# usbSimStepper_v1_0a.net
KiCad netlist of a schematic drawn in EAGLE
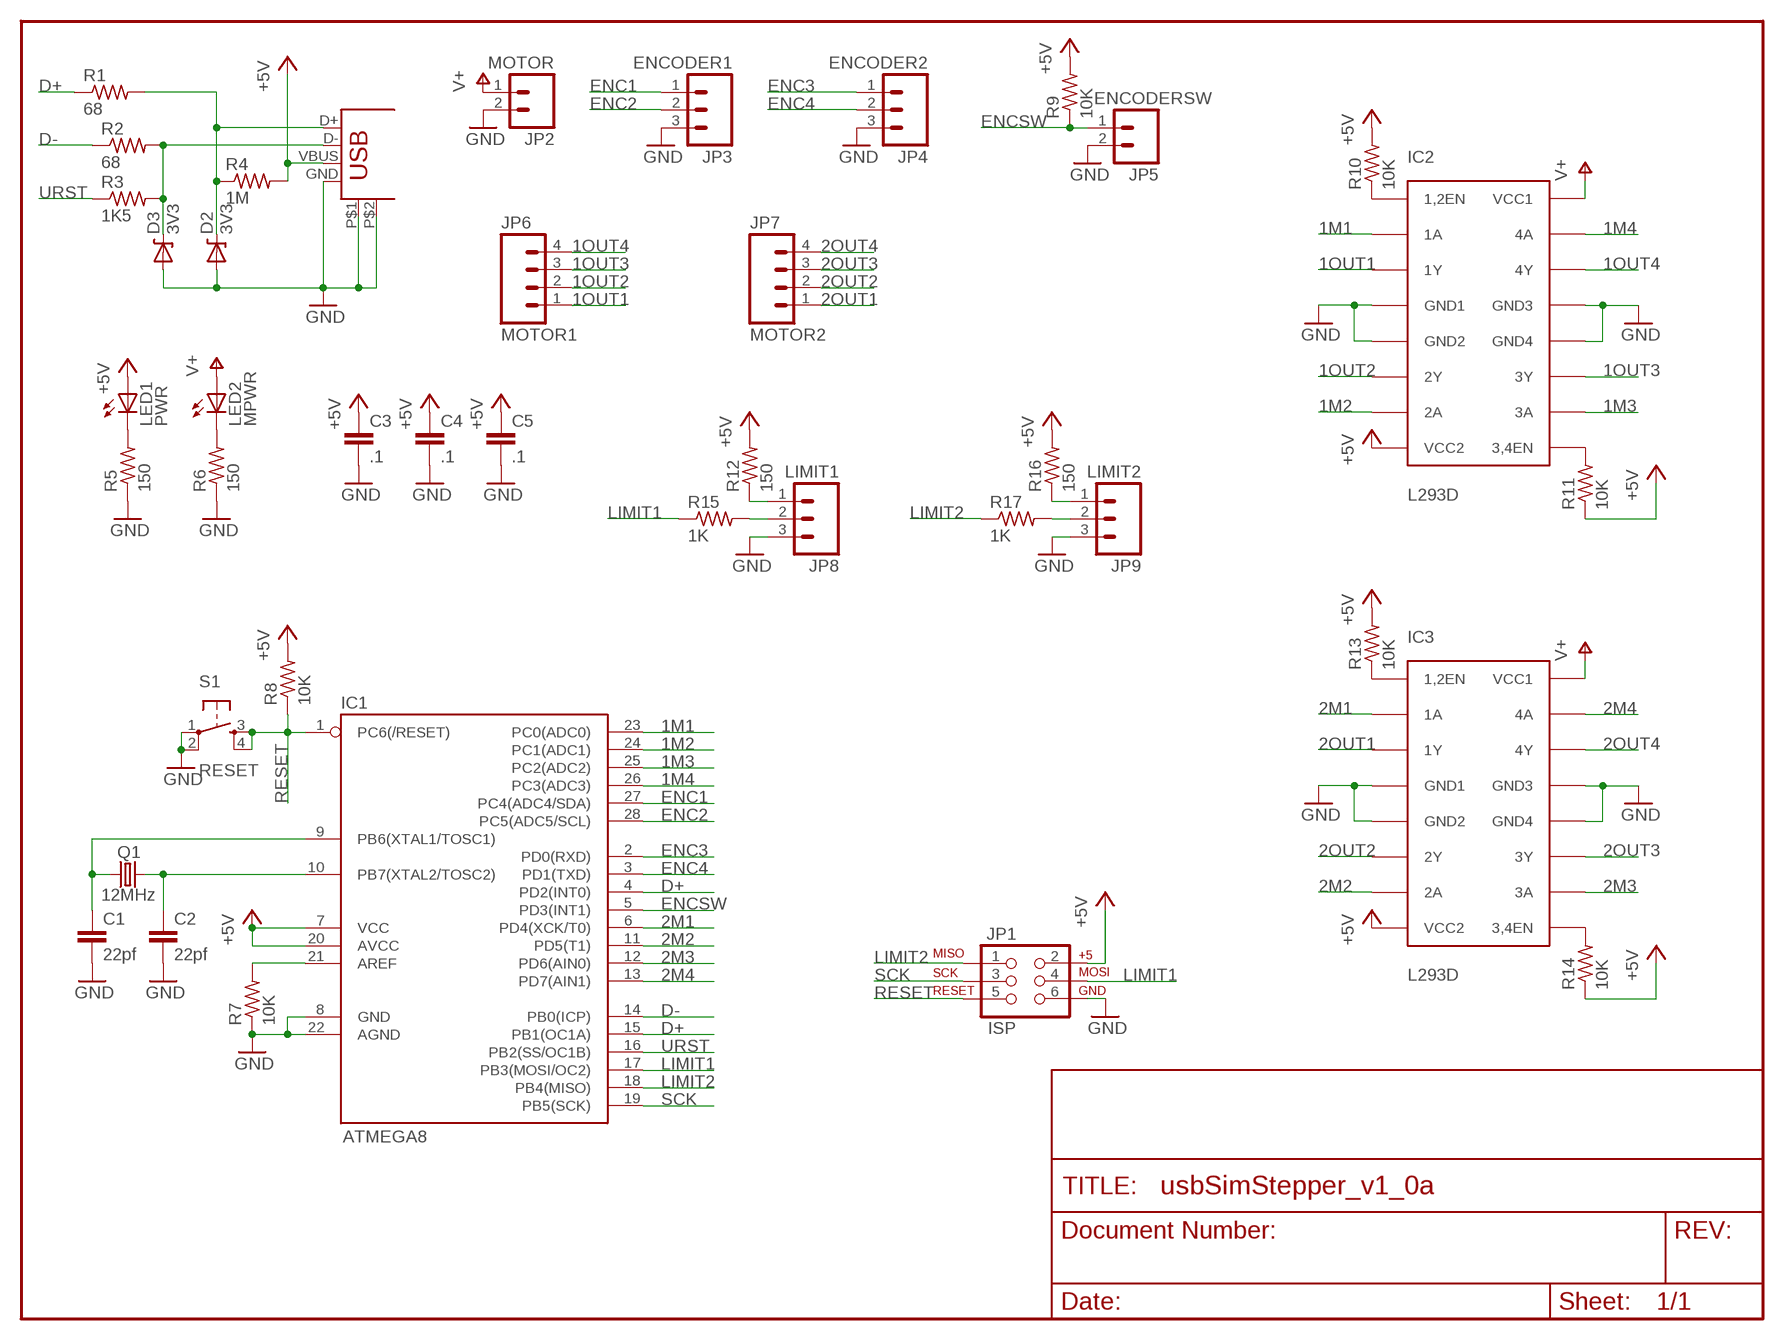
[diagram p0: schematic, sheet 1]

(export (version "E")
  (design (tool "Eeschema 10.0.6"))
  (components
    (comp (ref "C1")
      (value "22pf")
      (footprint "eagle-import:CAP-PTH-SMALL2")
      (libsource (lib "eagle-import") (part "CAPPTH2"))
    )
    (comp (ref "C2")
      (value "22pf")
      (footprint "eagle-import:CAP-PTH-SMALL2")
      (libsource (lib "eagle-import") (part "CAPPTH2"))
    )
    (comp (ref "C3")
      (value ".1")
      (footprint "eagle-import:CAP-PTH-SMALL2")
      (libsource (lib "eagle-import") (part "CAPPTH2"))
    )
    (comp (ref "C4")
      (value ".1")
      (footprint "eagle-import:CAP-PTH-SMALL2")
      (libsource (lib "eagle-import") (part "CAPPTH2"))
    )
    (comp (ref "C5")
      (value ".1")
      (footprint "eagle-import:CAP-PTH-SMALL2")
      (libsource (lib "eagle-import") (part "CAPPTH2"))
    )
    (comp (ref "D2")
      (value "3V3")
      (footprint "eagle-import:DIODE-ZENER")
      (libsource (lib "eagle-import") (part "DIODE-ZENERPTH"))
    )
    (comp (ref "D3")
      (value "3V3")
      (footprint "eagle-import:DIODE-ZENER")
      (libsource (lib "eagle-import") (part "DIODE-ZENERPTH"))
    )
    (comp (ref "IC1")
      (value "ATMEGA8")
      (footprint "eagle-import:DIL28-3")
      (libsource (lib "eagle-import") (part "AVR-MEGA8-PPTH"))
    )
    (comp (ref "IC2")
      (value "L293D")
      (footprint "eagle-import:DIL16")
      (libsource (lib "eagle-import") (part "L293D"))
    )
    (comp (ref "IC3")
      (value "L293D")
      (footprint "eagle-import:DIL16")
      (libsource (lib "eagle-import") (part "L293D"))
    )
    (comp (ref "JP1")
      (value "ISP")
      (footprint "eagle-import:2X3-NS")
      (libsource (lib "eagle-import") (part "AVR_SPI_PRG_6NS"))
    )
    (comp (ref "JP2")
      (value "MOTOR")
      (footprint "eagle-import:MOLEX-1X2")
      (libsource (lib "eagle-import") (part "M02POLAR"))
    )
    (comp (ref "JP3")
      (value "ENCODER1")
      (footprint "eagle-import:MOLEX-1X3")
      (libsource (lib "eagle-import") (part "M03POLAR"))
    )
    (comp (ref "JP4")
      (value "ENCODER2")
      (footprint "eagle-import:MOLEX-1X3")
      (libsource (lib "eagle-import") (part "M03POLAR"))
    )
    (comp (ref "JP5")
      (value "ENCODERSW")
      (footprint "eagle-import:MOLEX-1X2")
      (libsource (lib "eagle-import") (part "M02POLAR"))
    )
    (comp (ref "JP6")
      (value "MOTOR1")
      (footprint "eagle-import:MOLEX-1X4")
      (libsource (lib "eagle-import") (part "M04POLAR"))
    )
    (comp (ref "JP7")
      (value "MOTOR2")
      (footprint "eagle-import:MOLEX-1X4")
      (libsource (lib "eagle-import") (part "M04POLAR"))
    )
    (comp (ref "JP8")
      (value "LIMIT1")
      (footprint "eagle-import:MOLEX-1X3")
      (libsource (lib "eagle-import") (part "M03POLAR"))
    )
    (comp (ref "JP9")
      (value "LIMIT2")
      (footprint "eagle-import:MOLEX-1X3")
      (libsource (lib "eagle-import") (part "M03POLAR"))
    )
    (comp (ref "LED1")
      (value "PWR")
      (footprint "eagle-import:LED5MM")
      (libsource (lib "eagle-import") (part "LED5MM"))
    )
    (comp (ref "LED2")
      (value "MPWR")
      (footprint "eagle-import:LED5MM")
      (libsource (lib "eagle-import") (part "LED5MM"))
    )
    (comp (ref "Q1")
      (value "12MHz")
      (footprint "eagle-import:HC49US")
      (libsource (lib "eagle-import") (part "CRYSTALHC49US"))
    )
    (comp (ref "R1")
      (value "68")
      (footprint "eagle-import:0204_7")
      (libsource (lib "eagle-import") (part "R-US_0204/7"))
    )
    (comp (ref "R2")
      (value "68")
      (footprint "eagle-import:0204_7")
      (libsource (lib "eagle-import") (part "R-US_0204/7"))
    )
    (comp (ref "R3")
      (value "1K5")
      (footprint "eagle-import:0204_7")
      (libsource (lib "eagle-import") (part "R-US_0204/7"))
    )
    (comp (ref "R4")
      (value "1M")
      (footprint "eagle-import:0204_7")
      (libsource (lib "eagle-import") (part "R-US_0204/7"))
    )
    (comp (ref "R5")
      (value "150")
      (footprint "eagle-import:0204_7")
      (libsource (lib "eagle-import") (part "R-US_0204/7"))
    )
    (comp (ref "R6")
      (value "150")
      (footprint "eagle-import:0204_7")
      (libsource (lib "eagle-import") (part "R-US_0204/7"))
    )
    (comp (ref "R7")
      (value "10K")
      (footprint "eagle-import:0204_7")
      (libsource (lib "eagle-import") (part "R-US_0204/7"))
    )
    (comp (ref "R8")
      (value "10K")
      (footprint "eagle-import:0204_7")
      (libsource (lib "eagle-import") (part "R-US_0204/7"))
    )
    (comp (ref "R9")
      (value "10K")
      (footprint "eagle-import:0204_7")
      (libsource (lib "eagle-import") (part "R-US_0204/7"))
    )
    (comp (ref "R10")
      (value "10K")
      (footprint "eagle-import:0204_7")
      (libsource (lib "eagle-import") (part "R-US_0204/7"))
    )
    (comp (ref "R11")
      (value "10K")
      (footprint "eagle-import:0204_7")
      (libsource (lib "eagle-import") (part "R-US_0204/7"))
    )
    (comp (ref "R12")
      (value "150")
      (footprint "eagle-import:0204_7")
      (libsource (lib "eagle-import") (part "R-US_0204/7"))
    )
    (comp (ref "R13")
      (value "10K")
      (footprint "eagle-import:0204_7")
      (libsource (lib "eagle-import") (part "R-US_0204/7"))
    )
    (comp (ref "R14")
      (value "10K")
      (footprint "eagle-import:0204_7")
      (libsource (lib "eagle-import") (part "R-US_0204/7"))
    )
    (comp (ref "R15")
      (value "1K")
      (footprint "eagle-import:0204_7")
      (libsource (lib "eagle-import") (part "R-US_0204/7"))
    )
    (comp (ref "R16")
      (value "150")
      (footprint "eagle-import:0204_7")
      (libsource (lib "eagle-import") (part "R-US_0204/7"))
    )
    (comp (ref "R17")
      (value "1K")
      (footprint "eagle-import:0204_7")
      (libsource (lib "eagle-import") (part "R-US_0204/7"))
    )
    (comp (ref "S1")
      (value "RESET")
      (footprint "eagle-import:TACTILE-PTH")
      (libsource (lib "eagle-import") (part "TAC_SWITCHPTH"))
    )
    (comp (ref "X1")
      (value "USB")
      (footprint "eagle-import:USB-B-PTH-VERTICAL")
      (libsource (lib "eagle-import") (part "USB+SHIELDUSB-B-PTH-VERTICAL+SHIELD"))
    )
  )
  (nets
    (net (code "1") (name "+5V") (class "Default")
      (node (ref "C3") (pin "1") (pinfunction "1_1") (pintype "passive"))
      (node (ref "C4") (pin "1") (pinfunction "1_1") (pintype "passive"))
      (node (ref "C5") (pin "1") (pinfunction "1_1") (pintype "passive"))
      (node (ref "IC1") (pin "20") (pinfunction "AVCC_20") (pintype "bidirectional"))
      (node (ref "IC1") (pin "7") (pinfunction "VCC_7") (pintype "bidirectional"))
      (node (ref "IC2") (pin "8") (pinfunction "VCC2_8") (pintype "power_in"))
      (node (ref "IC3") (pin "8") (pinfunction "VCC2_8") (pintype "power_in"))
      (node (ref "JP1") (pin "2") (pinfunction "2_2") (pintype "passive"))
      (node (ref "LED1") (pin "A") (pinfunction "A_A") (pintype "passive"))
      (node (ref "R10") (pin "2") (pinfunction "2_2") (pintype "passive"))
      (node (ref "R11") (pin "1") (pinfunction "1_1") (pintype "passive"))
      (node (ref "R12") (pin "2") (pinfunction "2_2") (pintype "passive"))
      (node (ref "R13") (pin "2") (pinfunction "2_2") (pintype "passive"))
      (node (ref "R14") (pin "1") (pinfunction "1_1") (pintype "passive"))
      (node (ref "R16") (pin "2") (pinfunction "2_2") (pintype "passive"))
      (node (ref "R4") (pin "2") (pinfunction "2_2") (pintype "passive"))
      (node (ref "R8") (pin "2") (pinfunction "2_2") (pintype "passive"))
      (node (ref "R9") (pin "2") (pinfunction "2_2") (pintype "passive"))
      (node (ref "X1") (pin "VBUS") (pinfunction "VBUS_VBUS") (pintype "bidirectional"))
    )
    (net (code "2") (name "/1M1") (class "Default")
      (node (ref "IC1") (pin "23") (pinfunction "PC0(ADC0)_23") (pintype "bidirectional"))
      (node (ref "IC2") (pin "2") (pinfunction "1A_2") (pintype "input"))
    )
    (net (code "3") (name "/1M2") (class "Default")
      (node (ref "IC1") (pin "24") (pinfunction "PC1(ADC1)_24") (pintype "bidirectional"))
      (node (ref "IC2") (pin "7") (pinfunction "2A_7") (pintype "input"))
    )
    (net (code "4") (name "/1M3") (class "Default")
      (node (ref "IC1") (pin "25") (pinfunction "PC2(ADC2)_25") (pintype "bidirectional"))
      (node (ref "IC2") (pin "10") (pinfunction "3A_10") (pintype "input"))
    )
    (net (code "5") (name "/1M4") (class "Default")
      (node (ref "IC1") (pin "26") (pinfunction "PC3(ADC3)_26") (pintype "bidirectional"))
      (node (ref "IC2") (pin "15") (pinfunction "4A_15") (pintype "input"))
    )
    (net (code "6") (name "/1OUT1") (class "Default")
      (node (ref "IC2") (pin "3") (pinfunction "1Y_3") (pintype "output"))
      (node (ref "JP6") (pin "1") (pinfunction "1_1") (pintype "passive"))
    )
    (net (code "7") (name "/1OUT2") (class "Default")
      (node (ref "IC2") (pin "6") (pinfunction "2Y_6") (pintype "output"))
      (node (ref "JP6") (pin "2") (pinfunction "2_2") (pintype "passive"))
    )
    (net (code "8") (name "/1OUT3") (class "Default")
      (node (ref "IC2") (pin "11") (pinfunction "3Y_11") (pintype "output"))
      (node (ref "JP6") (pin "3") (pinfunction "3_3") (pintype "passive"))
    )
    (net (code "9") (name "/1OUT4") (class "Default")
      (node (ref "IC2") (pin "14") (pinfunction "4Y_14") (pintype "output"))
      (node (ref "JP6") (pin "4") (pinfunction "4_4") (pintype "passive"))
    )
    (net (code "10") (name "/2M1") (class "Default")
      (node (ref "IC1") (pin "6") (pinfunction "PD4(XCK/T0)_6") (pintype "bidirectional"))
      (node (ref "IC3") (pin "2") (pinfunction "1A_2") (pintype "input"))
    )
    (net (code "11") (name "/2M2") (class "Default")
      (node (ref "IC1") (pin "11") (pinfunction "PD5(T1)_11") (pintype "bidirectional"))
      (node (ref "IC3") (pin "7") (pinfunction "2A_7") (pintype "input"))
    )
    (net (code "12") (name "/2M3") (class "Default")
      (node (ref "IC1") (pin "12") (pinfunction "PD6(AIN0)_12") (pintype "bidirectional"))
      (node (ref "IC3") (pin "10") (pinfunction "3A_10") (pintype "input"))
    )
    (net (code "13") (name "/2M4") (class "Default")
      (node (ref "IC1") (pin "13") (pinfunction "PD7(AIN1)_13") (pintype "bidirectional"))
      (node (ref "IC3") (pin "15") (pinfunction "4A_15") (pintype "input"))
    )
    (net (code "14") (name "/2OUT1") (class "Default")
      (node (ref "IC3") (pin "3") (pinfunction "1Y_3") (pintype "output"))
      (node (ref "JP7") (pin "1") (pinfunction "1_1") (pintype "passive"))
    )
    (net (code "15") (name "/2OUT2") (class "Default")
      (node (ref "IC3") (pin "6") (pinfunction "2Y_6") (pintype "output"))
      (node (ref "JP7") (pin "2") (pinfunction "2_2") (pintype "passive"))
    )
    (net (code "16") (name "/2OUT3") (class "Default")
      (node (ref "IC3") (pin "11") (pinfunction "3Y_11") (pintype "output"))
      (node (ref "JP7") (pin "3") (pinfunction "3_3") (pintype "passive"))
    )
    (net (code "17") (name "/2OUT4") (class "Default")
      (node (ref "IC3") (pin "14") (pinfunction "4Y_14") (pintype "output"))
      (node (ref "JP7") (pin "4") (pinfunction "4_4") (pintype "passive"))
    )
    (net (code "18") (name "/D+") (class "Default")
      (node (ref "IC1") (pin "15") (pinfunction "PB1(OC1A)_15") (pintype "bidirectional"))
      (node (ref "IC1") (pin "4") (pinfunction "PD2(INT0)_4") (pintype "bidirectional"))
      (node (ref "R1") (pin "1") (pinfunction "1_1") (pintype "passive"))
    )
    (net (code "19") (name "/D-") (class "Default")
      (node (ref "IC1") (pin "14") (pinfunction "PB0(ICP)_14") (pintype "bidirectional"))
      (node (ref "R2") (pin "1") (pinfunction "1_1") (pintype "passive"))
    )
    (net (code "20") (name "/ENC1") (class "Default")
      (node (ref "IC1") (pin "27") (pinfunction "PC4(ADC4/SDA)_27") (pintype "bidirectional"))
      (node (ref "JP3") (pin "1") (pinfunction "1_1") (pintype "passive"))
    )
    (net (code "21") (name "/ENC2") (class "Default")
      (node (ref "IC1") (pin "28") (pinfunction "PC5(ADC5/SCL)_28") (pintype "bidirectional"))
      (node (ref "JP3") (pin "2") (pinfunction "2_2") (pintype "passive"))
    )
    (net (code "22") (name "/ENC3") (class "Default")
      (node (ref "IC1") (pin "2") (pinfunction "PD0(RXD)_2") (pintype "bidirectional"))
      (node (ref "JP4") (pin "1") (pinfunction "1_1") (pintype "passive"))
    )
    (net (code "23") (name "/ENC4") (class "Default")
      (node (ref "IC1") (pin "3") (pinfunction "PD1(TXD)_3") (pintype "bidirectional"))
      (node (ref "JP4") (pin "2") (pinfunction "2_2") (pintype "passive"))
    )
    (net (code "24") (name "/ENCSW") (class "Default")
      (node (ref "IC1") (pin "5") (pinfunction "PD3(INT1)_5") (pintype "bidirectional"))
      (node (ref "JP5") (pin "1") (pinfunction "1_1") (pintype "passive"))
      (node (ref "R9") (pin "1") (pinfunction "1_1") (pintype "passive"))
    )
    (net (code "25") (name "/LIMIT1") (class "Default")
      (node (ref "IC1") (pin "17") (pinfunction "PB3(MOSI/OC2)_17") (pintype "bidirectional"))
      (node (ref "JP1") (pin "4") (pinfunction "4_4") (pintype "passive"))
      (node (ref "R15") (pin "1") (pinfunction "1_1") (pintype "passive"))
    )
    (net (code "26") (name "/LIMIT2") (class "Default")
      (node (ref "IC1") (pin "18") (pinfunction "PB4(MISO)_18") (pintype "bidirectional"))
      (node (ref "JP1") (pin "1") (pinfunction "1_1") (pintype "passive"))
      (node (ref "R17") (pin "1") (pinfunction "1_1") (pintype "passive"))
    )
    (net (code "27") (name "/RESET") (class "Default")
      (node (ref "IC1") (pin "1") (pinfunction "PC6(/RESET)_1") (pintype "bidirectional"))
      (node (ref "JP1") (pin "5") (pinfunction "5_5") (pintype "passive"))
      (node (ref "R8") (pin "1") (pinfunction "1_1") (pintype "passive"))
      (node (ref "S1") (pin "3") (pinfunction "3_3") (pintype "passive"))
      (node (ref "S1") (pin "4") (pinfunction "4_4") (pintype "passive"))
    )
    (net (code "28") (name "/SCK") (class "Default")
      (node (ref "IC1") (pin "19") (pinfunction "PB5(SCK)_19") (pintype "bidirectional"))
      (node (ref "JP1") (pin "3") (pinfunction "3_3") (pintype "passive"))
    )
    (net (code "29") (name "/URST") (class "Default")
      (node (ref "IC1") (pin "16") (pinfunction "PB2(SS/OC1B)_16") (pintype "bidirectional"))
      (node (ref "R3") (pin "1") (pinfunction "1_1") (pintype "passive"))
    )
    (net (code "30") (name "GND") (class "Default")
      (node (ref "C1") (pin "2") (pinfunction "2_2") (pintype "passive"))
      (node (ref "C2") (pin "2") (pinfunction "2_2") (pintype "passive"))
      (node (ref "C3") (pin "2") (pinfunction "2_2") (pintype "passive"))
      (node (ref "C4") (pin "2") (pinfunction "2_2") (pintype "passive"))
      (node (ref "C5") (pin "2") (pinfunction "2_2") (pintype "passive"))
      (node (ref "D2") (pin "P$2") (pinfunction "A_P$2") (pintype "passive"))
      (node (ref "D3") (pin "P$2") (pinfunction "A_P$2") (pintype "passive"))
      (node (ref "IC1") (pin "22") (pinfunction "AGND_22") (pintype "bidirectional"))
      (node (ref "IC1") (pin "8") (pinfunction "GND_8") (pintype "bidirectional"))
      (node (ref "IC2") (pin "12") (pinfunction "GND4_12") (pintype "power_in"))
      (node (ref "IC2") (pin "13") (pinfunction "GND3_13") (pintype "power_in"))
      (node (ref "IC2") (pin "4") (pinfunction "GND1_4") (pintype "power_in"))
      (node (ref "IC2") (pin "5") (pinfunction "GND2_5") (pintype "power_in"))
      (node (ref "IC3") (pin "12") (pinfunction "GND4_12") (pintype "power_in"))
      (node (ref "IC3") (pin "13") (pinfunction "GND3_13") (pintype "power_in"))
      (node (ref "IC3") (pin "4") (pinfunction "GND1_4") (pintype "power_in"))
      (node (ref "IC3") (pin "5") (pinfunction "GND2_5") (pintype "power_in"))
      (node (ref "JP1") (pin "6") (pinfunction "6_6") (pintype "passive"))
      (node (ref "JP2") (pin "2") (pinfunction "2_2") (pintype "passive"))
      (node (ref "JP3") (pin "3") (pinfunction "3_3") (pintype "passive"))
      (node (ref "JP4") (pin "3") (pinfunction "3_3") (pintype "passive"))
      (node (ref "JP5") (pin "2") (pinfunction "2_2") (pintype "passive"))
      (node (ref "JP8") (pin "3") (pinfunction "3_3") (pintype "passive"))
      (node (ref "JP9") (pin "3") (pinfunction "3_3") (pintype "passive"))
      (node (ref "R5") (pin "1") (pinfunction "1_1") (pintype "passive"))
      (node (ref "R6") (pin "1") (pinfunction "1_1") (pintype "passive"))
      (node (ref "R7") (pin "1") (pinfunction "1_1") (pintype "passive"))
      (node (ref "S1") (pin "1") (pinfunction "1_1") (pintype "passive"))
      (node (ref "S1") (pin "2") (pinfunction "2_2") (pintype "passive"))
      (node (ref "X1") (pin "GND") (pinfunction "GND_GND") (pintype "bidirectional"))
      (node (ref "X1") (pin "P$1") (pinfunction "P$1_P$1") (pintype "bidirectional"))
      (node (ref "X1") (pin "P$2") (pinfunction "P$2_P$2") (pintype "bidirectional"))
    )
    (net (code "31") (name "Net-(D2-C)") (class "Default")
      (node (ref "D2") (pin "P$1") (pinfunction "C_P$1") (pintype "passive"))
      (node (ref "R1") (pin "2") (pinfunction "2_2") (pintype "passive"))
      (node (ref "R4") (pin "1") (pinfunction "1_1") (pintype "passive"))
      (node (ref "X1") (pin "D+") (pinfunction "D+_D+") (pintype "bidirectional"))
    )
    (net (code "32") (name "Net-(D3-C)") (class "Default")
      (node (ref "D3") (pin "P$1") (pinfunction "C_P$1") (pintype "passive"))
      (node (ref "R2") (pin "2") (pinfunction "2_2") (pintype "passive"))
      (node (ref "R3") (pin "2") (pinfunction "2_2") (pintype "passive"))
      (node (ref "X1") (pin "D-") (pinfunction "D-_D-") (pintype "bidirectional"))
    )
    (net (code "33") (name "Net-(IC1-AREF)") (class "Default")
      (node (ref "IC1") (pin "21") (pinfunction "AREF_21") (pintype "bidirectional"))
      (node (ref "R7") (pin "2") (pinfunction "2_2") (pintype "passive"))
    )
    (net (code "34") (name "Net-(IC1-PB6(XTAL1{slash}TOSC1))") (class "Default")
      (node (ref "C1") (pin "1") (pinfunction "1_1") (pintype "passive"))
      (node (ref "IC1") (pin "9") (pinfunction "PB6(XTAL1/TOSC1)_9") (pintype "bidirectional"))
      (node (ref "Q1") (pin "1") (pinfunction "1_1") (pintype "passive"))
    )
    (net (code "35") (name "Net-(IC1-PB7(XTAL2{slash}TOSC2))") (class "Default")
      (node (ref "C2") (pin "1") (pinfunction "1_1") (pintype "passive"))
      (node (ref "IC1") (pin "10") (pinfunction "PB7(XTAL2/TOSC2)_10") (pintype "bidirectional"))
      (node (ref "Q1") (pin "2") (pinfunction "2_2") (pintype "passive"))
    )
    (net (code "36") (name "Net-(IC2-1,2EN)") (class "Default")
      (node (ref "IC2") (pin "1") (pinfunction "1,2EN_1") (pintype "input"))
      (node (ref "R10") (pin "1") (pinfunction "1_1") (pintype "passive"))
    )
    (net (code "37") (name "Net-(IC2-3,4EN)") (class "Default")
      (node (ref "IC2") (pin "9") (pinfunction "3,4EN_9") (pintype "input"))
      (node (ref "R11") (pin "2") (pinfunction "2_2") (pintype "passive"))
    )
    (net (code "38") (name "Net-(IC3-1,2EN)") (class "Default")
      (node (ref "IC3") (pin "1") (pinfunction "1,2EN_1") (pintype "input"))
      (node (ref "R13") (pin "1") (pinfunction "1_1") (pintype "passive"))
    )
    (net (code "39") (name "Net-(IC3-3,4EN)") (class "Default")
      (node (ref "IC3") (pin "9") (pinfunction "3,4EN_9") (pintype "input"))
      (node (ref "R14") (pin "2") (pinfunction "2_2") (pintype "passive"))
    )
    (net (code "40") (name "Net-(JP8-Pad1)") (class "Default")
      (node (ref "JP8") (pin "1") (pinfunction "1_1") (pintype "passive"))
      (node (ref "R12") (pin "1") (pinfunction "1_1") (pintype "passive"))
    )
    (net (code "41") (name "Net-(JP8-Pad2)") (class "Default")
      (node (ref "JP8") (pin "2") (pinfunction "2_2") (pintype "passive"))
      (node (ref "R15") (pin "2") (pinfunction "2_2") (pintype "passive"))
    )
    (net (code "42") (name "Net-(JP9-Pad1)") (class "Default")
      (node (ref "JP9") (pin "1") (pinfunction "1_1") (pintype "passive"))
      (node (ref "R16") (pin "1") (pinfunction "1_1") (pintype "passive"))
    )
    (net (code "43") (name "Net-(JP9-Pad2)") (class "Default")
      (node (ref "JP9") (pin "2") (pinfunction "2_2") (pintype "passive"))
      (node (ref "R17") (pin "2") (pinfunction "2_2") (pintype "passive"))
    )
    (net (code "44") (name "Net-(LED1-C)") (class "Default")
      (node (ref "LED1") (pin "K") (pinfunction "C_K") (pintype "passive"))
      (node (ref "R5") (pin "2") (pinfunction "2_2") (pintype "passive"))
    )
    (net (code "45") (name "Net-(LED2-C)") (class "Default")
      (node (ref "LED2") (pin "K") (pinfunction "C_K") (pintype "passive"))
      (node (ref "R6") (pin "2") (pinfunction "2_2") (pintype "passive"))
    )
    (net (code "46") (name "V+") (class "Default")
      (node (ref "IC2") (pin "16") (pinfunction "VCC1_16") (pintype "power_in"))
      (node (ref "IC3") (pin "16") (pinfunction "VCC1_16") (pintype "power_in"))
      (node (ref "JP2") (pin "1") (pinfunction "1_1") (pintype "passive"))
      (node (ref "LED2") (pin "A") (pinfunction "A_A") (pintype "passive"))
    )
  )
)
